# f1control.net
KiCad netlist of a schematic drawn in EAGLE
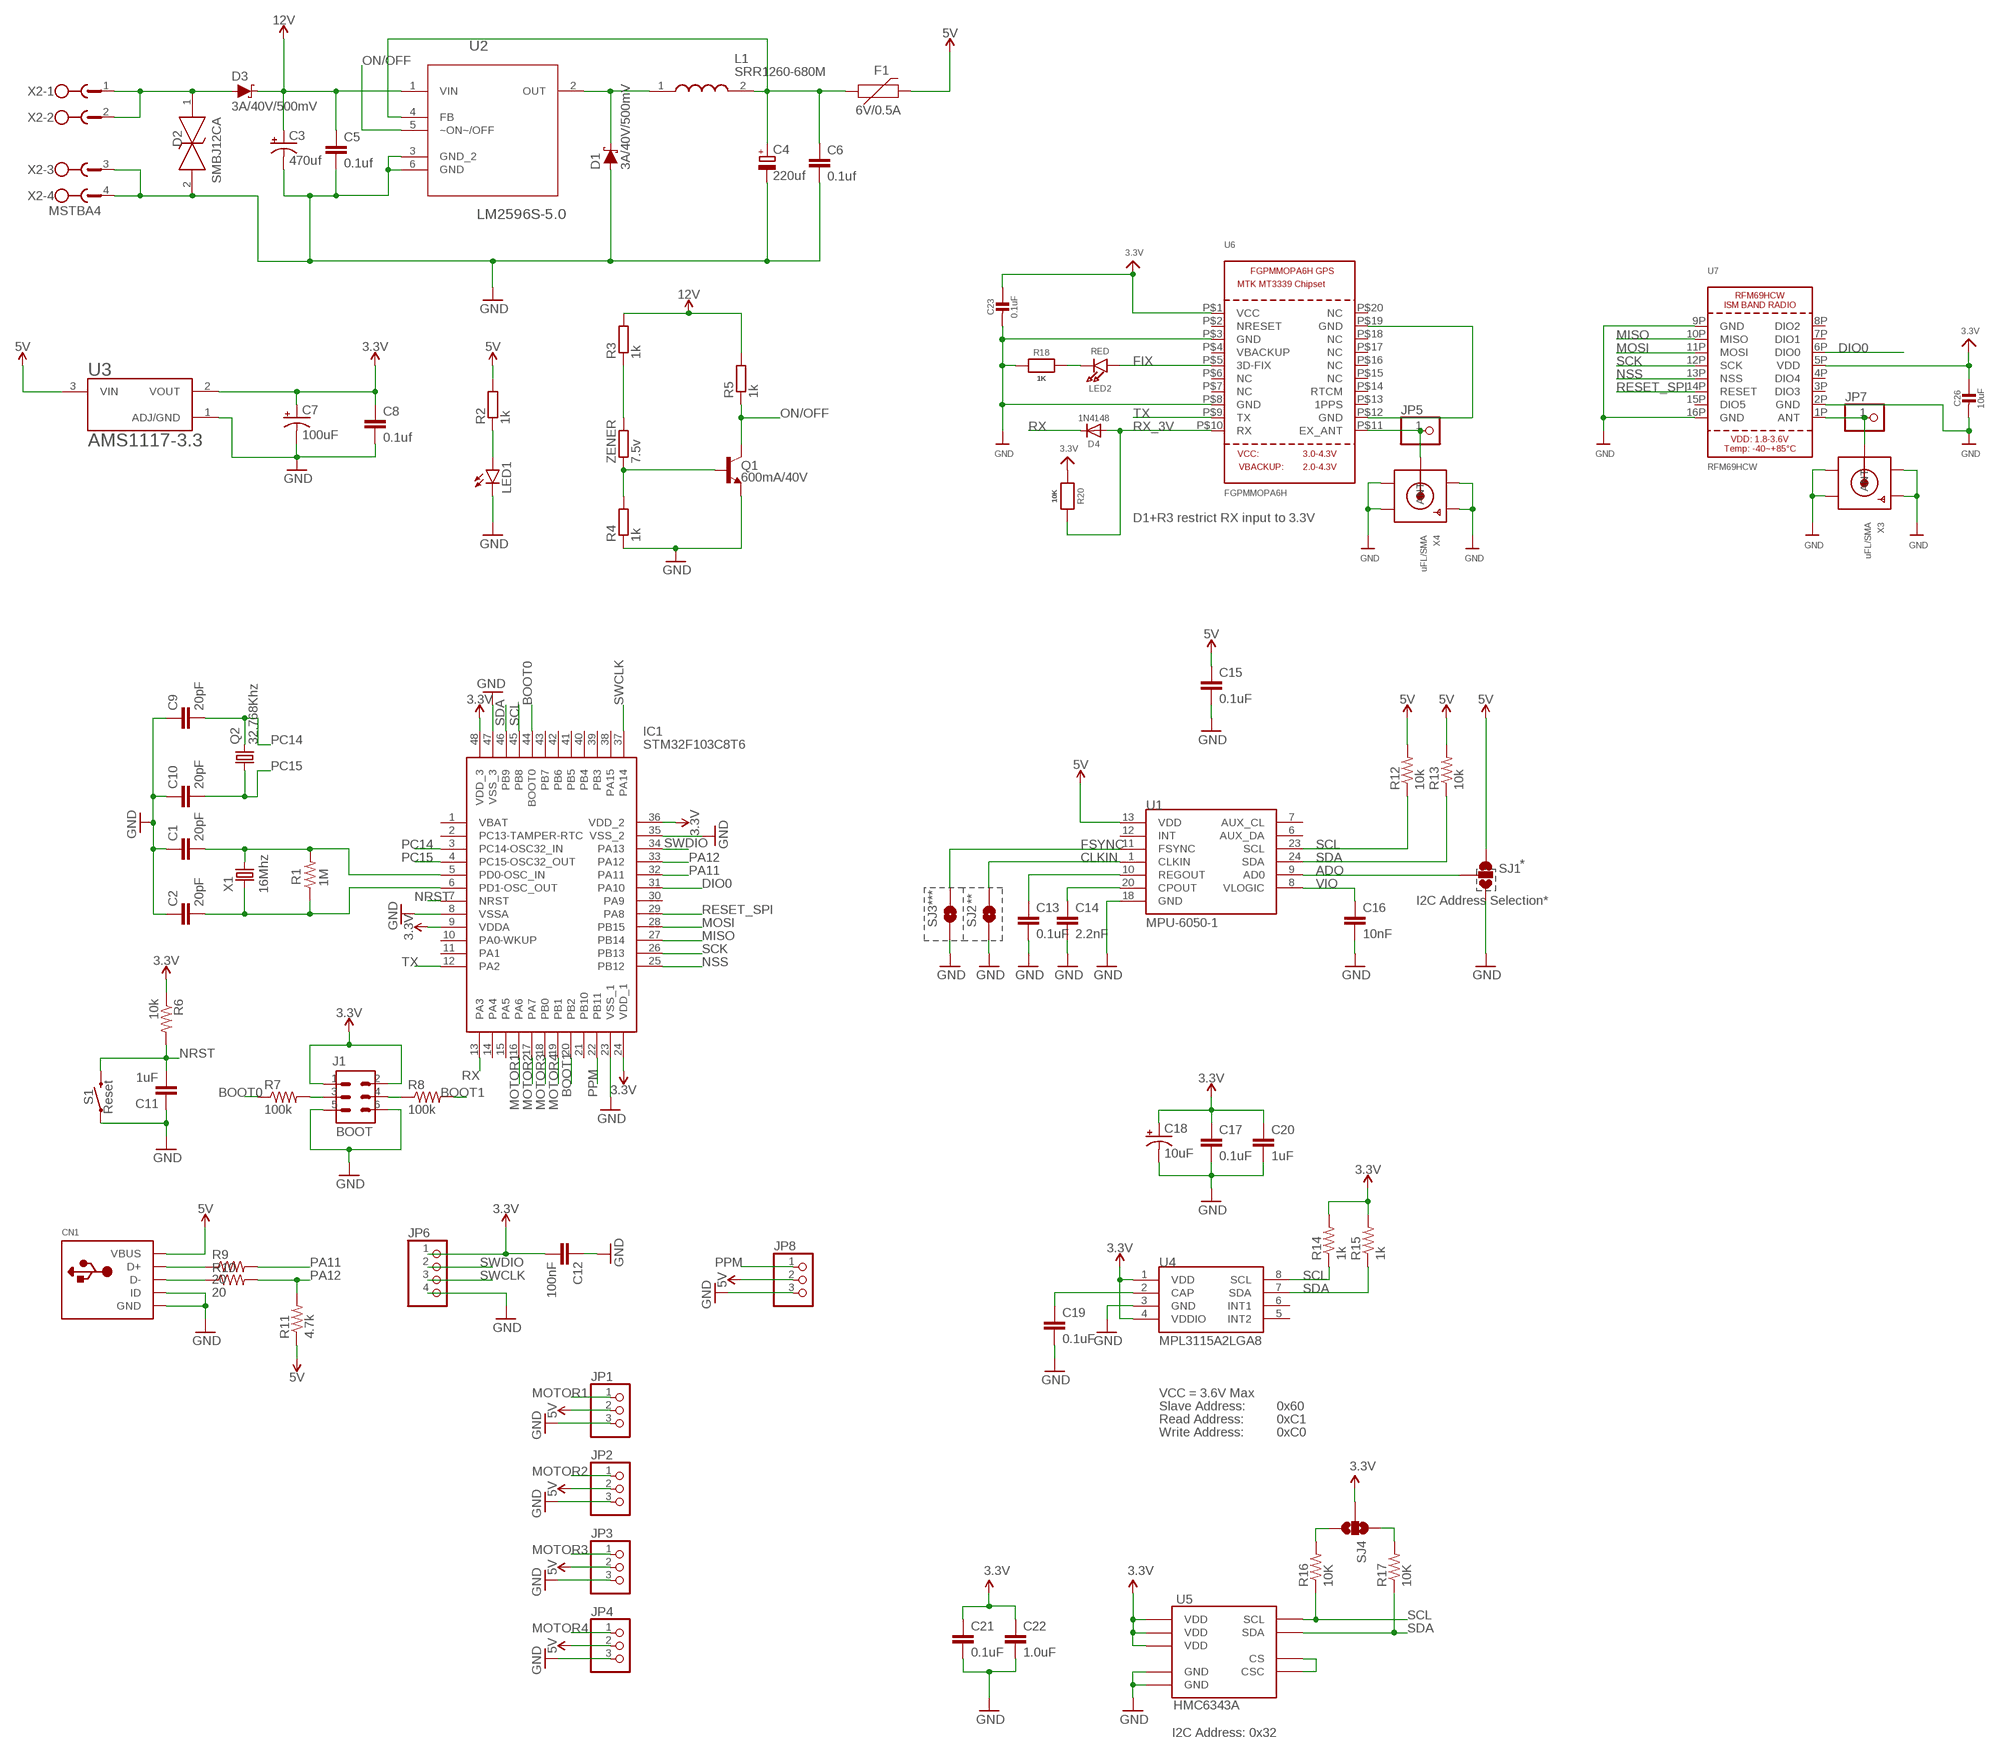
[diagram p0: schematic, sheet 1]

(export (version "E")
  (design (tool "Eeschema 10.0.6"))
  (components
    (comp (ref "C1")
      (value "20pF")
      (footprint "eagle-import:C0603")
      (libsource (lib "eagle-import") (part "C-EUC0603"))
    )
    (comp (ref "C2")
      (value "20pF")
      (footprint "eagle-import:C0603")
      (libsource (lib "eagle-import") (part "C-EUC0603"))
    )
    (comp (ref "C3")
      (value "470uf")
      (footprint "eagle-import:E5-8,5")
      (libsource (lib "eagle-import") (part "CPOL-USE5-8.5"))
    )
    (comp (ref "C4")
      (value "220uf")
      (footprint "eagle-import:153CLV-1014")
      (libsource (lib "eagle-import") (part "CPOL-EU153CLV-1014"))
    )
    (comp (ref "C5")
      (value "0.1uf")
      (footprint "eagle-import:C0805")
      (libsource (lib "eagle-import") (part "C-EUC0805"))
    )
    (comp (ref "C6")
      (value "0.1uf")
      (footprint "eagle-import:C0805")
      (libsource (lib "eagle-import") (part "C-EUC0805"))
    )
    (comp (ref "C7")
      (value "100uF")
      (footprint "eagle-import:NIC_10X10.5_CAP")
      (libsource (lib "eagle-import") (part "100UF-POLAR-10X10.5-63V-20%"))
    )
    (comp (ref "C8")
      (value "0.1uf")
      (footprint "eagle-import:C0805")
      (libsource (lib "eagle-import") (part "C-EUC0805"))
    )
    (comp (ref "C9")
      (value "20pF")
      (footprint "eagle-import:C0603")
      (libsource (lib "eagle-import") (part "C-EUC0603"))
    )
    (comp (ref "C10")
      (value "20pF")
      (footprint "eagle-import:C0603")
      (libsource (lib "eagle-import") (part "C-EUC0603"))
    )
    (comp (ref "C11")
      (value "1uF")
      (footprint "eagle-import:C0603")
      (libsource (lib "eagle-import") (part "C-EUC0603"))
    )
    (comp (ref "C12")
      (value "100nF")
      (footprint "eagle-import:C0603")
      (libsource (lib "eagle-import") (part "C-EUC0603"))
    )
    (comp (ref "C13")
      (value "0.1uF")
      (footprint "eagle-import:0603-CAP")
      (libsource (lib "eagle-import") (part "CAP0603-CAP"))
    )
    (comp (ref "C14")
      (value "2.2nF")
      (footprint "eagle-import:0603-CAP")
      (libsource (lib "eagle-import") (part "CAP0603-CAP"))
    )
    (comp (ref "C15")
      (value "0.1uF")
      (footprint "eagle-import:0603-CAP")
      (libsource (lib "eagle-import") (part "CAP0603-CAP"))
    )
    (comp (ref "C16")
      (value "10nF")
      (footprint "eagle-import:0603-CAP")
      (libsource (lib "eagle-import") (part "CAP0603-CAP"))
    )
    (comp (ref "C17")
      (value "0.1uF")
      (footprint "eagle-import:0402-CAP")
      (libsource (lib "eagle-import") (part "CAP0402-CAP"))
    )
    (comp (ref "C18")
      (value "10uF")
      (footprint "eagle-import:EIA3216")
      (libsource (lib "eagle-import") (part "CAP_POL1206"))
    )
    (comp (ref "C19")
      (value "0.1uF")
      (footprint "eagle-import:0402-CAP")
      (libsource (lib "eagle-import") (part "CAP0402-CAP"))
    )
    (comp (ref "C20")
      (value "1uF")
      (footprint "eagle-import:0402-CAP")
      (libsource (lib "eagle-import") (part "CAP0402-CAP"))
    )
    (comp (ref "C21")
      (value "0.1uF")
      (footprint "eagle-import:0603-CAP")
      (libsource (lib "eagle-import") (part "0.1UF-25V(+80/-20%)(0603)"))
    )
    (comp (ref "C22")
      (value "1.0uF")
      (footprint "eagle-import:0603-CAP")
      (libsource (lib "eagle-import") (part "1.0UF-16V-10%(0603)"))
    )
    (comp (ref "C23")
      (value "0.1uF")
      (footprint "eagle-import:0805-NO")
      (libsource (lib "eagle-import") (part "CAP_CERAMIC0805-NOOUTLINE"))
    )
    (comp (ref "C26")
      (value "10uF")
      (footprint "eagle-import:0805-NO")
      (libsource (lib "eagle-import") (part "CAP_CERAMIC0805-NOOUTLINE"))
    )
    (comp (ref "CN1")
      (value "USBMINIB")
      (footprint "eagle-import:USB-MINIB")
      (libsource (lib "eagle-import") (part "USBMINIB"))
    )
    (comp (ref "D1")
      (value "3A/40V/500mV")
      (footprint "eagle-import:SMA-DIODE")
      (libsource (lib "eagle-import") (part "DIODE-SCHOTTKY-B340A"))
    )
    (comp (ref "D2")
      (value "SMBJ12CA")
      (footprint "eagle-import:DIONM5443X244N")
      (fields (field (name "MOUSER_PART_NUMBER") "652-SMBJ12CA"))
      (libsource (lib "eagle-import") (part "SMBJ12CA"))
    )
    (comp (ref "D3")
      (value "3A/40V/500mV")
      (footprint "eagle-import:SMA-DIODE")
      (libsource (lib "eagle-import") (part "DIODE-SCHOTTKY-B340A"))
    )
    (comp (ref "D4")
      (value "1N4148")
      (footprint "eagle-import:SOD-323")
      (libsource (lib "eagle-import") (part "DIODESOD-323"))
    )
    (comp (ref "F1")
      (value "6V/0.5A")
      (footprint "eagle-import:1206")
      (libsource (lib "eagle-import") (part "PPTC_HALF-AMP"))
    )
    (comp (ref "IC1")
      (value "STM32F103C8T6")
      (footprint "eagle-import:QFP50P900X900X160-48N")
      (fields
        (field (name "MOUSER_PART_NUMBER") "511-STM32F103C8T6")
        (field (name "RS_PART_NUMBER") "0402279P")
      )
      (libsource (lib "eagle-import") (part "STM32F103C8T6"))
    )
    (comp (ref "J1")
      (value "BOOT")
      (footprint "eagle-import:621006245821")
      (fields
        (field (name "MANUFACTURER") "Wurth Elektronik")
        (field (name "MPN") "621006245821")
        (field (name "CREATED_BY") "PCBLayout.com")
      )
      (libsource (lib "eagle-import") (part "621006245821"))
    )
    (comp (ref "JP1")
      (value "PINHD-1X3")
      (footprint "eagle-import:1X03")
      (libsource (lib "eagle-import") (part "PINHD-1X3"))
    )
    (comp (ref "JP2")
      (value "PINHD-1X3")
      (footprint "eagle-import:1X03")
      (libsource (lib "eagle-import") (part "PINHD-1X3"))
    )
    (comp (ref "JP3")
      (value "PINHD-1X3")
      (footprint "eagle-import:1X03")
      (libsource (lib "eagle-import") (part "PINHD-1X3"))
    )
    (comp (ref "JP4")
      (value "PINHD-1X3")
      (footprint "eagle-import:1X03")
      (libsource (lib "eagle-import") (part "PINHD-1X3"))
    )
    (comp (ref "JP5")
      (value "HEADER-1X1ROUND")
      (footprint "eagle-import:1X01_ROUND")
      (libsource (lib "eagle-import") (part "HEADER-1X1ROUND"))
    )
    (comp (ref "JP6")
      (value "PINHD-1X4")
      (footprint "eagle-import:1X04")
      (libsource (lib "eagle-import") (part "PINHD-1X4"))
    )
    (comp (ref "JP7")
      (value "HEADER-1X1ROUND")
      (footprint "eagle-import:1X01_ROUND")
      (libsource (lib "eagle-import") (part "HEADER-1X1ROUND"))
    )
    (comp (ref "JP8")
      (value "PINHD-1X3")
      (footprint "eagle-import:1X03")
      (libsource (lib "eagle-import") (part "PINHD-1X3"))
    )
    (comp (ref "L1")
      (value "SRR1260-680M")
      (footprint "eagle-import:INDPM125125X650N")
      (fields
        (field (name "MOUSER_PART_NUMBER") "652-SRR1260-680M")
        (field (name "RS_PART_NUMBER") "7272243P")
      )
      (libsource (lib "eagle-import") (part "SRR1260-680M"))
    )
    (comp (ref "LED1")
      (value "LEDCHIP-LED0805")
      (footprint "eagle-import:CHIP-LED0805")
      (libsource (lib "eagle-import") (part "LEDCHIP-LED0805"))
    )
    (comp (ref "LED2")
      (value "RED")
      (footprint "eagle-import:CHIPLED_0805")
      (libsource (lib "eagle-import") (part "LED0805"))
    )
    (comp (ref "Q1")
      (value "600mA/40V")
      (footprint "eagle-import:SOT23-3")
      (libsource (lib "eagle-import") (part "TRANS_NPN-MMBT2222AL"))
    )
    (comp (ref "Q2")
      (value "32.768Khz")
      (footprint "eagle-import:MC-306")
      (fields (field (name "MPN") "MC-306 60.0KHZ  100PPM ,12.5PF"))
      (libsource (lib "eagle-import") (part "MC-306"))
    )
    (comp (ref "R1")
      (value "1M")
      (footprint "eagle-import:R0603")
      (libsource (lib "eagle-import") (part "R-US_R0603"))
    )
    (comp (ref "R2")
      (value "1k")
      (footprint "eagle-import:R0805")
      (libsource (lib "eagle-import") (part "R-EU_R0805"))
    )
    (comp (ref "R3")
      (value "1k")
      (footprint "eagle-import:R0805")
      (libsource (lib "eagle-import") (part "R-EU_R0805"))
    )
    (comp (ref "R4")
      (value "1k")
      (footprint "eagle-import:R0805")
      (libsource (lib "eagle-import") (part "R-EU_R0805"))
    )
    (comp (ref "R5")
      (value "1k")
      (footprint "eagle-import:R0805")
      (libsource (lib "eagle-import") (part "R-EU_R0805"))
    )
    (comp (ref "R6")
      (value "10k")
      (footprint "eagle-import:R0603")
      (libsource (lib "eagle-import") (part "R-US_R0603"))
    )
    (comp (ref "R7")
      (value "100k")
      (footprint "eagle-import:R0603")
      (libsource (lib "eagle-import") (part "R-US_R0603"))
    )
    (comp (ref "R8")
      (value "100k")
      (footprint "eagle-import:R0603")
      (libsource (lib "eagle-import") (part "R-US_R0603"))
    )
    (comp (ref "R9")
      (value "20")
      (footprint "eagle-import:R0603")
      (libsource (lib "eagle-import") (part "R-US_R0603"))
    )
    (comp (ref "R10")
      (value "20")
      (footprint "eagle-import:R0603")
      (libsource (lib "eagle-import") (part "R-US_R0603"))
    )
    (comp (ref "R11")
      (value "4.7k")
      (footprint "eagle-import:R0603")
      (libsource (lib "eagle-import") (part "R-US_R0603"))
    )
    (comp (ref "R12")
      (value "10k")
      (footprint "eagle-import:0603-RES")
      (libsource (lib "eagle-import") (part "RESISTOR0603-RES"))
    )
    (comp (ref "R13")
      (value "10k")
      (footprint "eagle-import:0603-RES")
      (libsource (lib "eagle-import") (part "RESISTOR0603-RES"))
    )
    (comp (ref "R14")
      (value "1k")
      (footprint "eagle-import:0402-RES")
      (libsource (lib "eagle-import") (part "RESISTOR0402-RES"))
    )
    (comp (ref "R15")
      (value "1k")
      (footprint "eagle-import:0402-RES")
      (libsource (lib "eagle-import") (part "RESISTOR0402-RES"))
    )
    (comp (ref "R16")
      (value "10K")
      (footprint "eagle-import:0603-RES")
      (libsource (lib "eagle-import") (part "10KOHM1/10W1%(0603)0603"))
    )
    (comp (ref "R17")
      (value "10K")
      (footprint "eagle-import:0603-RES")
      (libsource (lib "eagle-import") (part "10KOHM1/10W1%(0603)0603"))
    )
    (comp (ref "R18")
      (value "1K")
      (footprint "eagle-import:0805-NO")
      (libsource (lib "eagle-import") (part "RESISTOR0805_NOOUTLINE"))
    )
    (comp (ref "R20")
      (value "10K")
      (footprint "eagle-import:0805-NO")
      (libsource (lib "eagle-import") (part "RESISTOR0805_NOOUTLINE"))
    )
    (comp (ref "S1")
      (value "Reset")
      (footprint "eagle-import:TACTILE_SWITCH_SMD_4.5MM")
      (libsource (lib "eagle-import") (part "MOMENTARY-SWITCH-SPST-SMD-4.5MM"))
    )
    (comp (ref "SJ1")
      (value "SOLDERJUMPER_2WAYPASTE2&3")
      (footprint "eagle-import:SJ_3_PASTE2&3")
      (libsource (lib "eagle-import") (part "SOLDERJUMPER_2WAYPASTE2&3"))
    )
    (comp (ref "SJ2")
      (value "SOLDERJUMPERTRACE")
      (footprint "eagle-import:SJ_2S-TRACE")
      (libsource (lib "eagle-import") (part "SOLDERJUMPERTRACE"))
    )
    (comp (ref "SJ3")
      (value "SOLDERJUMPERTRACE")
      (footprint "eagle-import:SJ_2S-TRACE")
      (libsource (lib "eagle-import") (part "SOLDERJUMPERTRACE"))
    )
    (comp (ref "SJ4")
      (value "SOLDERJUMPER_2WAYPASTE1&2&3")
      (footprint "eagle-import:SJ_3_PASTE1&2&3")
      (libsource (lib "eagle-import") (part "SOLDERJUMPER_2WAYPASTE1&2&3"))
    )
    (comp (ref "U1")
      (value "MPU-6050-1")
      (footprint "eagle-import:QFN-24-4MM2")
      (libsource (lib "eagle-import") (part "MPU-6050-1"))
    )
    (comp (ref "U2")
      (value "LM2596S-5.0")
      (footprint "eagle-import:TO170P1435X465-6N")
      (fields (field (name "MF") "Texas"))
      (libsource (lib "eagle-import") (part "LM2596S-5.0"))
    )
    (comp (ref "U3")
      (value "AMS1117-3.3")
      (footprint "eagle-import:SOT229P700X180-4N")
      (fields (field (name "MF") "Advanced Monolithic Systems"))
      (libsource (lib "eagle-import") (part "AMS1117-3.3"))
    )
    (comp (ref "U4")
      (value "MPL3115A2LGA8")
      (footprint "eagle-import:LGA8")
      (libsource (lib "eagle-import") (part "MPL3115A2LGA8"))
    )
    (comp (ref "U5")
      (value "HMC6343A")
      (footprint "eagle-import:LCC36")
      (libsource (lib "eagle-import") (part "HMC6343A"))
    )
    (comp (ref "U6")
      (value "FGPMMOPA6H")
      (footprint "eagle-import:FGPMMOPA6H")
      (libsource (lib "eagle-import") (part "GPS_FGPMMOPA6H"))
    )
    (comp (ref "U7")
      (value "RFM69HCW")
      (footprint "eagle-import:RFMHCW_SMT")
      (libsource (lib "eagle-import") (part "RFM69HCW_SMT"))
    )
    (comp (ref "X1")
      (value "16Mhz")
      (footprint "eagle-import:XTAL_HC49")
      (fields
        (field (name "MANUFACTURER") "Xinhunjing ")
        (field (name "MPN") "49S/18PF")
        (field (name "CREATED_BY") "PCBLayout.com")
      )
      (libsource (lib "eagle-import") (part "49S/18PF"))
    )
    (comp (ref "X2")
      (value "MSTBA4")
      (footprint "eagle-import:MSTBA4")
      (fields (field (name "MF") "FARNELL") (field (name "MPN") "1757268"))
      (libsource (lib "eagle-import") (part "MSTBA4"))
    )
    (comp (ref "X3")
      (value "uFL/SMA")
      (footprint "eagle-import:SMA_EDGELAUNCH_UFL")
      (libsource (lib "eagle-import") (part "SMACONNECTOR_EDGE_UFL"))
    )
    (comp (ref "X4")
      (value "uFL/SMA")
      (footprint "eagle-import:SMA_EDGELAUNCH_UFL")
      (libsource (lib "eagle-import") (part "SMACONNECTOR_EDGE_UFL"))
    )
    (comp (ref "ZENER")
      (value "7.5v")
      (footprint "eagle-import:0204_7")
      (libsource (lib "eagle-import") (part "R-EU_0204/7"))
    )
  )
  (nets
    (net (code "1") (name "/ADO") (class "Default")
      (node (ref "SJ1") (pin "2") (pinfunction "2_2") (pintype "passive"))
      (node (ref "U1") (pin "9") (pinfunction "AD0_9") (pintype "bidirectional"))
    )
    (net (code "2") (name "/BOOT0") (class "Default")
      (node (ref "IC1") (pin "44") (pinfunction "BOOT0_44") (pintype "bidirectional"))
      (node (ref "R7") (pin "1") (pinfunction "1_1") (pintype "passive"))
    )
    (net (code "3") (name "/BOOT1") (class "Default")
      (node (ref "IC1") (pin "20") (pinfunction "PB2_20") (pintype "bidirectional"))
      (node (ref "R8") (pin "2") (pinfunction "2_2") (pintype "passive"))
    )
    (net (code "4") (name "/CLKIN") (class "Default")
      (node (ref "SJ2") (pin "2") (pinfunction "2_2") (pintype "passive"))
      (node (ref "U1") (pin "1") (pinfunction "CLKIN_1") (pintype "bidirectional"))
    )
    (net (code "5") (name "/DIO0") (class "Default")
      (node (ref "IC1") (pin "31") (pinfunction "PA10_31") (pintype "bidirectional"))
      (node (ref "U7") (pin "6P") (pinfunction "DIO0_6P") (pintype "bidirectional"))
    )
    (net (code "6") (name "/FIX") (class "Default")
      (node (ref "LED2") (pin "A") (pinfunction "A_A") (pintype "passive"))
      (node (ref "U6") (pin "P$5") (pinfunction "3D-FIX_P$5") (pintype "bidirectional"))
    )
    (net (code "7") (name "/FSYNC") (class "Default")
      (node (ref "SJ3") (pin "2") (pinfunction "2_2") (pintype "passive"))
      (node (ref "U1") (pin "11") (pinfunction "FSYNC_11") (pintype "bidirectional"))
    )
    (net (code "8") (name "/MISO") (class "Default")
      (node (ref "IC1") (pin "27") (pinfunction "PB14_27") (pintype "bidirectional"))
      (node (ref "U7") (pin "10P") (pinfunction "MISO_10P") (pintype "output"))
    )
    (net (code "9") (name "/MOSI") (class "Default")
      (node (ref "IC1") (pin "28") (pinfunction "PB15_28") (pintype "bidirectional"))
      (node (ref "U7") (pin "11P") (pinfunction "MOSI_11P") (pintype "input"))
    )
    (net (code "10") (name "/MOTOR1") (class "Default")
      (node (ref "IC1") (pin "16") (pinfunction "PA6_16") (pintype "bidirectional"))
      (node (ref "JP1") (pin "1") (pinfunction "1_1") (pintype "passive"))
    )
    (net (code "11") (name "/MOTOR2") (class "Default")
      (node (ref "IC1") (pin "17") (pinfunction "PA7_17") (pintype "bidirectional"))
      (node (ref "JP2") (pin "1") (pinfunction "1_1") (pintype "passive"))
    )
    (net (code "12") (name "/MOTOR3") (class "Default")
      (node (ref "IC1") (pin "18") (pinfunction "PB0_18") (pintype "bidirectional"))
      (node (ref "JP3") (pin "1") (pinfunction "1_1") (pintype "passive"))
    )
    (net (code "13") (name "/MOTOR4") (class "Default")
      (node (ref "IC1") (pin "19") (pinfunction "PB1_19") (pintype "bidirectional"))
      (node (ref "JP4") (pin "1") (pinfunction "1_1") (pintype "passive"))
    )
    (net (code "14") (name "/NRST") (class "Default")
      (node (ref "C11") (pin "2") (pinfunction "2_2") (pintype "passive"))
      (node (ref "IC1") (pin "7") (pinfunction "NRST_7") (pintype "input"))
      (node (ref "R6") (pin "2") (pinfunction "2_2") (pintype "passive"))
      (node (ref "S1") (pin "1") (pinfunction "2_1") (pintype "passive"))
      (node (ref "S1") (pin "4") (pinfunction "2_4") (pintype "passive"))
    )
    (net (code "15") (name "/NSS") (class "Default")
      (node (ref "IC1") (pin "25") (pinfunction "PB12_25") (pintype "bidirectional"))
      (node (ref "U7") (pin "13P") (pinfunction "NSS_13P") (pintype "input"))
    )
    (net (code "16") (name "/ON{slash}OFF") (class "Default")
      (node (ref "Q1") (pin "3") (pinfunction "C_3") (pintype "passive"))
      (node (ref "R5") (pin "1") (pinfunction "1_1") (pintype "passive"))
      (node (ref "U2") (pin "5") (pinfunction "~{ON}/OFF_5") (pintype "input"))
    )
    (net (code "17") (name "/PA11") (class "Default")
      (node (ref "IC1") (pin "32") (pinfunction "PA11_32") (pintype "bidirectional"))
      (node (ref "R9") (pin "2") (pinfunction "2_2") (pintype "passive"))
    )
    (net (code "18") (name "/PA12") (class "Default")
      (node (ref "IC1") (pin "33") (pinfunction "PA12_33") (pintype "bidirectional"))
      (node (ref "R10") (pin "2") (pinfunction "2_2") (pintype "passive"))
      (node (ref "R11") (pin "2") (pinfunction "2_2") (pintype "passive"))
    )
    (net (code "19") (name "/PC14") (class "Default")
      (node (ref "C9") (pin "2") (pinfunction "2_2") (pintype "passive"))
      (node (ref "IC1") (pin "3") (pinfunction "PC14-OSC32_IN_3") (pintype "input"))
      (node (ref "Q2") (pin "4") (pinfunction "2_4") (pintype "passive"))
    )
    (net (code "20") (name "/PC15") (class "Default")
      (node (ref "C10") (pin "2") (pinfunction "2_2") (pintype "passive"))
      (node (ref "IC1") (pin "4") (pinfunction "PC15-OSC32_OUT_4") (pintype "output"))
      (node (ref "Q2") (pin "1") (pinfunction "1_1") (pintype "passive"))
    )
    (net (code "21") (name "/PPM") (class "Default")
      (node (ref "IC1") (pin "22") (pinfunction "PB11_22") (pintype "bidirectional"))
      (node (ref "JP8") (pin "1") (pinfunction "1_1") (pintype "passive"))
    )
    (net (code "22") (name "/RESET_SPI") (class "Default")
      (node (ref "IC1") (pin "29") (pinfunction "PA8_29") (pintype "bidirectional"))
      (node (ref "U7") (pin "14P") (pinfunction "RESET_14P") (pintype "input"))
    )
    (net (code "23") (name "/RX") (class "Default")
      (node (ref "D4") (pin "C") (pinfunction "C_C") (pintype "passive"))
      (node (ref "IC1") (pin "13") (pinfunction "PA3_13") (pintype "bidirectional"))
    )
    (net (code "24") (name "/RX_3V") (class "Default")
      (node (ref "D4") (pin "A") (pinfunction "A_A") (pintype "passive"))
      (node (ref "R20") (pin "2") (pinfunction "2_2") (pintype "passive"))
      (node (ref "U6") (pin "P$10") (pinfunction "RX_P$10") (pintype "bidirectional"))
    )
    (net (code "25") (name "/SCK") (class "Default")
      (node (ref "IC1") (pin "26") (pinfunction "PB13_26") (pintype "bidirectional"))
      (node (ref "U7") (pin "12P") (pinfunction "SCK_12P") (pintype "input"))
    )
    (net (code "26") (name "/SCL") (class "Default")
      (node (ref "IC1") (pin "45") (pinfunction "PB8_45") (pintype "bidirectional"))
      (node (ref "R12") (pin "1") (pinfunction "1_1") (pintype "passive"))
      (node (ref "R14") (pin "1") (pinfunction "1_1") (pintype "passive"))
      (node (ref "R16") (pin "1") (pinfunction "1_1") (pintype "passive"))
      (node (ref "U1") (pin "23") (pinfunction "SCL_23") (pintype "bidirectional"))
      (node (ref "U4") (pin "8") (pinfunction "SCL_8") (pintype "bidirectional"))
      (node (ref "U5") (pin "32") (pinfunction "SCL_32") (pintype "bidirectional"))
    )
    (net (code "27") (name "/SDA") (class "Default")
      (node (ref "IC1") (pin "46") (pinfunction "PB9_46") (pintype "bidirectional"))
      (node (ref "R13") (pin "1") (pinfunction "1_1") (pintype "passive"))
      (node (ref "R15") (pin "1") (pinfunction "1_1") (pintype "passive"))
      (node (ref "R17") (pin "1") (pinfunction "1_1") (pintype "passive"))
      (node (ref "U1") (pin "24") (pinfunction "SDA_24") (pintype "bidirectional"))
      (node (ref "U4") (pin "7") (pinfunction "SDA_7") (pintype "bidirectional"))
      (node (ref "U5") (pin "36") (pinfunction "SDA_36") (pintype "bidirectional"))
    )
    (net (code "28") (name "/SWCLK") (class "Default")
      (node (ref "IC1") (pin "37") (pinfunction "PA14_37") (pintype "bidirectional"))
      (node (ref "JP6") (pin "3") (pinfunction "3_3") (pintype "passive"))
    )
    (net (code "29") (name "/SWDIO") (class "Default")
      (node (ref "IC1") (pin "34") (pinfunction "PA13_34") (pintype "bidirectional"))
      (node (ref "JP6") (pin "2") (pinfunction "2_2") (pintype "passive"))
    )
    (net (code "30") (name "/TX") (class "Default")
      (node (ref "IC1") (pin "12") (pinfunction "PA2_12") (pintype "bidirectional"))
      (node (ref "U6") (pin "P$9") (pinfunction "TX_P$9") (pintype "bidirectional"))
    )
    (net (code "31") (name "/VIO") (class "Default")
      (node (ref "C16") (pin "1") (pinfunction "1_1") (pintype "passive"))
      (node (ref "U1") (pin "8") (pinfunction "VLOGIC_8") (pintype "bidirectional"))
    )
    (net (code "32") (name "3.3V") (class "Default")
      (node (ref "C12") (pin "2") (pinfunction "2_2") (pintype "passive"))
      (node (ref "C17") (pin "1") (pinfunction "1_1") (pintype "passive"))
      (node (ref "C18") (pin "A") (pinfunction "+_A") (pintype "passive"))
      (node (ref "C20") (pin "1") (pinfunction "1_1") (pintype "passive"))
      (node (ref "C21") (pin "1") (pinfunction "1_1") (pintype "passive"))
      (node (ref "C22") (pin "1") (pinfunction "1_1") (pintype "passive"))
      (node (ref "C23") (pin "1") (pinfunction "1_1") (pintype "passive"))
      (node (ref "C26") (pin "1") (pinfunction "1_1") (pintype "passive"))
      (node (ref "C7") (pin "+") (pinfunction "+_+") (pintype "passive"))
      (node (ref "C8") (pin "1") (pinfunction "1_1") (pintype "passive"))
      (node (ref "IC1") (pin "24") (pinfunction "VDD_1_24") (pintype "power_in"))
      (node (ref "IC1") (pin "36") (pinfunction "VDD_2_36") (pintype "power_in"))
      (node (ref "IC1") (pin "48") (pinfunction "VDD_3_48") (pintype "power_in"))
      (node (ref "IC1") (pin "9") (pinfunction "VDDA_9") (pintype "power_in"))
      (node (ref "J1") (pin "1") (pinfunction "1_1") (pintype "passive"))
      (node (ref "J1") (pin "2") (pinfunction "2_2") (pintype "passive"))
      (node (ref "JP6") (pin "1") (pinfunction "1_1") (pintype "passive"))
      (node (ref "R14") (pin "2") (pinfunction "2_2") (pintype "passive"))
      (node (ref "R15") (pin "2") (pinfunction "2_2") (pintype "passive"))
      (node (ref "R20") (pin "1") (pinfunction "1_1") (pintype "passive"))
      (node (ref "R6") (pin "1") (pinfunction "1_1") (pintype "passive"))
      (node (ref "SJ4") (pin "2") (pinfunction "2_2") (pintype "passive"))
      (node (ref "U3") (pin "2") (pinfunction "VOUT_2") (pintype "output"))
      (node (ref "U4") (pin "1") (pinfunction "VDD_1") (pintype "bidirectional"))
      (node (ref "U4") (pin "4") (pinfunction "VDDIO_4") (pintype "bidirectional"))
      (node (ref "U5") (pin "11") (pinfunction "VDD_11") (pintype "bidirectional"))
      (node (ref "U5") (pin "21") (pinfunction "VDD_21") (pintype "bidirectional"))
      (node (ref "U5") (pin "3") (pinfunction "VDD_3") (pintype "bidirectional"))
      (node (ref "U6") (pin "P$1") (pinfunction "VCC_P$1") (pintype "bidirectional"))
      (node (ref "U7") (pin "5P") (pinfunction "VDD_5P") (pintype "power_in"))
    )
    (net (code "33") (name "5V") (class "Default")
      (node (ref "C15") (pin "1") (pinfunction "1_1") (pintype "passive"))
      (node (ref "CN1") (pin "VBUS") (pinfunction "VBUS_VBUS") (pintype "power_in"))
      (node (ref "F1") (pin "2") (pinfunction "2_2") (pintype "bidirectional"))
      (node (ref "JP1") (pin "2") (pinfunction "2_2") (pintype "passive"))
      (node (ref "JP2") (pin "2") (pinfunction "2_2") (pintype "passive"))
      (node (ref "JP3") (pin "2") (pinfunction "2_2") (pintype "passive"))
      (node (ref "JP4") (pin "2") (pinfunction "2_2") (pintype "passive"))
      (node (ref "JP8") (pin "2") (pinfunction "2_2") (pintype "passive"))
      (node (ref "R11") (pin "1") (pinfunction "1_1") (pintype "passive"))
      (node (ref "R12") (pin "2") (pinfunction "2_2") (pintype "passive"))
      (node (ref "R13") (pin "2") (pinfunction "2_2") (pintype "passive"))
      (node (ref "R2") (pin "2") (pinfunction "2_2") (pintype "passive"))
      (node (ref "SJ1") (pin "1") (pinfunction "1_1") (pintype "passive"))
      (node (ref "U1") (pin "13") (pinfunction "VDD_13") (pintype "bidirectional"))
      (node (ref "U3") (pin "3") (pinfunction "VIN_3") (pintype "input"))
    )
    (net (code "34") (name "12V") (class "Default")
      (node (ref "C3") (pin "+") (pinfunction "+_+") (pintype "passive"))
      (node (ref "C5") (pin "1") (pinfunction "1_1") (pintype "passive"))
      (node (ref "D3") (pin "C") (pinfunction "C_C") (pintype "passive"))
      (node (ref "R3") (pin "2") (pinfunction "2_2") (pintype "passive"))
      (node (ref "R5") (pin "2") (pinfunction "2_2") (pintype "passive"))
      (node (ref "U2") (pin "1") (pinfunction "VIN_1") (pintype "power_in"))
    )
    (net (code "35") (name "GND") (class "Default")
      (node (ref "C1") (pin "1") (pinfunction "1_1") (pintype "passive"))
      (node (ref "C10") (pin "1") (pinfunction "1_1") (pintype "passive"))
      (node (ref "C11") (pin "1") (pinfunction "1_1") (pintype "passive"))
      (node (ref "C12") (pin "1") (pinfunction "1_1") (pintype "passive"))
      (node (ref "C13") (pin "2") (pinfunction "2_2") (pintype "passive"))
      (node (ref "C14") (pin "2") (pinfunction "2_2") (pintype "passive"))
      (node (ref "C15") (pin "2") (pinfunction "2_2") (pintype "passive"))
      (node (ref "C16") (pin "2") (pinfunction "2_2") (pintype "passive"))
      (node (ref "C17") (pin "2") (pinfunction "2_2") (pintype "passive"))
      (node (ref "C18") (pin "C") (pinfunction "-_C") (pintype "passive"))
      (node (ref "C19") (pin "2") (pinfunction "2_2") (pintype "passive"))
      (node (ref "C2") (pin "1") (pinfunction "1_1") (pintype "passive"))
      (node (ref "C20") (pin "2") (pinfunction "2_2") (pintype "passive"))
      (node (ref "C21") (pin "2") (pinfunction "2_2") (pintype "passive"))
      (node (ref "C22") (pin "2") (pinfunction "2_2") (pintype "passive"))
      (node (ref "C23") (pin "2") (pinfunction "2_2") (pintype "passive"))
      (node (ref "C26") (pin "2") (pinfunction "2_2") (pintype "passive"))
      (node (ref "C3") (pin "-") (pinfunction "-_-") (pintype "passive"))
      (node (ref "C4") (pin "-") (pinfunction "-_-") (pintype "passive"))
      (node (ref "C5") (pin "2") (pinfunction "2_2") (pintype "passive"))
      (node (ref "C6") (pin "2") (pinfunction "2_2") (pintype "passive"))
      (node (ref "C7") (pin "-") (pinfunction "-_-") (pintype "passive"))
      (node (ref "C8") (pin "2") (pinfunction "2_2") (pintype "passive"))
      (node (ref "C9") (pin "1") (pinfunction "1_1") (pintype "passive"))
      (node (ref "CN1") (pin "GND") (pinfunction "GND_GND") (pintype "power_in"))
      (node (ref "CN1") (pin "ID") (pinfunction "ID_ID") (pintype "bidirectional"))
      (node (ref "D1") (pin "A") (pinfunction "A_A") (pintype "passive"))
      (node (ref "D2") (pin "2") (pinfunction "2_2") (pintype "bidirectional"))
      (node (ref "IC1") (pin "23") (pinfunction "VSS_1_23") (pintype "power_in"))
      (node (ref "IC1") (pin "35") (pinfunction "VSS_2_35") (pintype "power_in"))
      (node (ref "IC1") (pin "47") (pinfunction "VSS_3_47") (pintype "power_in"))
      (node (ref "IC1") (pin "8") (pinfunction "VSSA_8") (pintype "power_in"))
      (node (ref "J1") (pin "5") (pinfunction "5_5") (pintype "passive"))
      (node (ref "J1") (pin "6") (pinfunction "6_6") (pintype "passive"))
      (node (ref "JP1") (pin "3") (pinfunction "3_3") (pintype "passive"))
      (node (ref "JP2") (pin "3") (pinfunction "3_3") (pintype "passive"))
      (node (ref "JP3") (pin "3") (pinfunction "3_3") (pintype "passive"))
      (node (ref "JP4") (pin "3") (pinfunction "3_3") (pintype "passive"))
      (node (ref "JP6") (pin "4") (pinfunction "4_4") (pintype "passive"))
      (node (ref "JP8") (pin "3") (pinfunction "3_3") (pintype "passive"))
      (node (ref "LED1") (pin "C") (pinfunction "C_C") (pintype "passive"))
      (node (ref "Q1") (pin "2") (pinfunction "E_2") (pintype "passive"))
      (node (ref "R18") (pin "1") (pinfunction "1_1") (pintype "passive"))
      (node (ref "R4") (pin "1") (pinfunction "1_1") (pintype "passive"))
      (node (ref "S1") (pin "2") (pinfunction "1_2") (pintype "passive"))
      (node (ref "S1") (pin "3") (pinfunction "1_3") (pintype "passive"))
      (node (ref "SJ1") (pin "3") (pinfunction "3_3") (pintype "passive"))
      (node (ref "SJ2") (pin "1") (pinfunction "1_1") (pintype "passive"))
      (node (ref "SJ3") (pin "1") (pinfunction "1_1") (pintype "passive"))
      (node (ref "U1") (pin "18") (pinfunction "GND_18") (pintype "bidirectional"))
      (node (ref "U2") (pin "3") (pinfunction "GND_2_3") (pintype "passive"))
      (node (ref "U2") (pin "6") (pinfunction "GND_6") (pintype "passive"))
      (node (ref "U3") (pin "1") (pinfunction "ADJ/GND_1") (pintype "power_in"))
      (node (ref "U4") (pin "3") (pinfunction "GND_3") (pintype "bidirectional"))
      (node (ref "U5") (pin "25") (pinfunction "GND_25") (pintype "bidirectional"))
      (node (ref "U5") (pin "29") (pinfunction "GND_29") (pintype "bidirectional"))
      (node (ref "U6") (pin "P$3") (pinfunction "GND_P$3") (pintype "bidirectional"))
      (node (ref "U6") (pin "P$8") (pinfunction "GND_P$8") (pintype "bidirectional"))
      (node (ref "U7") (pin "16P") (pinfunction "GND_16P") (pintype "power_in"))
      (node (ref "U7") (pin "2P") (pinfunction "GND_2P") (pintype "power_in"))
      (node (ref "U7") (pin "9P") (pinfunction "GND_9P") (pintype "power_in"))
      (node (ref "X2") (pin "3") (pinfunction "1_3") (pintype "passive"))
      (node (ref "X2") (pin "4") (pinfunction "1_4") (pintype "passive"))
      (node (ref "X3") (pin "GND@1") (pinfunction "GND1_GND@1") (pintype "power_in"))
      (node (ref "X3") (pin "GND@2") (pinfunction "GND2_GND@2") (pintype "power_in"))
      (node (ref "X3") (pin "GND@3") (pinfunction "GND3_GND@3") (pintype "power_in"))
      (node (ref "X3") (pin "GND@4") (pinfunction "GND4_GND@4") (pintype "power_in"))
      (node (ref "X4") (pin "GND@1") (pinfunction "GND1_GND@1") (pintype "power_in"))
      (node (ref "X4") (pin "GND@2") (pinfunction "GND2_GND@2") (pintype "power_in"))
      (node (ref "X4") (pin "GND@3") (pinfunction "GND3_GND@3") (pintype "power_in"))
      (node (ref "X4") (pin "GND@4") (pinfunction "GND4_GND@4") (pintype "power_in"))
    )
    (net (code "36") (name "Net-(CN1-PadD+)") (class "Default")
      (node (ref "CN1") (pin "D+") (pinfunction "D+_D+") (pintype "bidirectional"))
      (node (ref "R9") (pin "1") (pinfunction "1_1") (pintype "passive"))
    )
    (net (code "37") (name "Net-(CN1-PadD-)") (class "Default")
      (node (ref "CN1") (pin "D-") (pinfunction "D-_D-") (pintype "bidirectional"))
      (node (ref "R10") (pin "1") (pinfunction "1_1") (pintype "passive"))
    )
    (net (code "38") (name "Net-(IC1-PD0-OSC_IN)") (class "Default")
      (node (ref "C1") (pin "2") (pinfunction "2_2") (pintype "passive"))
      (node (ref "IC1") (pin "5") (pinfunction "PD0-OSC_IN_5") (pintype "input"))
      (node (ref "R1") (pin "2") (pinfunction "2_2") (pintype "passive"))
      (node (ref "X1") (pin "2") (pinfunction "2_2") (pintype "passive"))
    )
    (net (code "39") (name "Net-(IC1-PD1-OSC_OUT)") (class "Default")
      (node (ref "C2") (pin "2") (pinfunction "2_2") (pintype "passive"))
      (node (ref "IC1") (pin "6") (pinfunction "PD1-OSC_OUT_6") (pintype "output"))
      (node (ref "R1") (pin "1") (pinfunction "1_1") (pintype "passive"))
      (node (ref "X1") (pin "1") (pinfunction "1_1") (pintype "passive"))
    )
    (net (code "40") (name "Net-(J1-Pad3)") (class "Default")
      (node (ref "J1") (pin "3") (pinfunction "3_3") (pintype "passive"))
      (node (ref "R7") (pin "2") (pinfunction "2_2") (pintype "passive"))
    )
    (net (code "41") (name "Net-(J1-Pad4)") (class "Default")
      (node (ref "J1") (pin "4") (pinfunction "4_4") (pintype "passive"))
      (node (ref "R8") (pin "1") (pinfunction "1_1") (pintype "passive"))
    )
    (net (code "42") (name "Net-(LED1-PadA)") (class "Default")
      (node (ref "LED1") (pin "A") (pinfunction "A_A") (pintype "passive"))
      (node (ref "R2") (pin "1") (pinfunction "1_1") (pintype "passive"))
    )
    (net (code "43") (name "Net-(LED2-PadC)") (class "Default")
      (node (ref "LED2") (pin "C") (pinfunction "C_C") (pintype "passive"))
      (node (ref "R18") (pin "2") (pinfunction "2_2") (pintype "passive"))
    )
    (net (code "44") (name "Net-(Q1-B)") (class "Default")
      (node (ref "Q1") (pin "1") (pinfunction "B_1") (pintype "passive"))
      (node (ref "R4") (pin "2") (pinfunction "2_2") (pintype "passive"))
      (node (ref "ZENER") (pin "1") (pinfunction "1_1") (pintype "passive"))
    )
    (net (code "45") (name "Net-(R3-Pad1)") (class "Default")
      (node (ref "R3") (pin "1") (pinfunction "1_1") (pintype "passive"))
      (node (ref "ZENER") (pin "2") (pinfunction "2_2") (pintype "passive"))
    )
    (net (code "46") (name "Net-(R16-Pad2)") (class "Default")
      (node (ref "R16") (pin "2") (pinfunction "2_2") (pintype "passive"))
      (node (ref "SJ4") (pin "3") (pinfunction "3_3") (pintype "passive"))
    )
    (net (code "47") (name "Net-(R17-Pad2)") (class "Default")
      (node (ref "R17") (pin "2") (pinfunction "2_2") (pintype "passive"))
      (node (ref "SJ4") (pin "1") (pinfunction "1_1") (pintype "passive"))
    )
    (net (code "48") (name "Net-(U1-CPOUT)") (class "Default")
      (node (ref "C14") (pin "1") (pinfunction "1_1") (pintype "passive"))
      (node (ref "U1") (pin "20") (pinfunction "CPOUT_20") (pintype "bidirectional"))
    )
    (net (code "49") (name "Net-(U1-REGOUT)") (class "Default")
      (node (ref "C13") (pin "1") (pinfunction "1_1") (pintype "passive"))
      (node (ref "U1") (pin "10") (pinfunction "REGOUT_10") (pintype "bidirectional"))
    )
    (net (code "50") (name "Net-(U2-FB)") (class "Default")
      (node (ref "C4") (pin "+") (pinfunction "+_+") (pintype "passive"))
      (node (ref "C6") (pin "1") (pinfunction "1_1") (pintype "passive"))
      (node (ref "F1") (pin "1") (pinfunction "1_1") (pintype "bidirectional"))
      (node (ref "L1") (pin "2") (pinfunction "2_2") (pintype "bidirectional"))
      (node (ref "U2") (pin "4") (pinfunction "FB_4") (pintype "input"))
    )
    (net (code "51") (name "Net-(U2-OUT)") (class "Default")
      (node (ref "D1") (pin "C") (pinfunction "C_C") (pintype "passive"))
      (node (ref "L1") (pin "1") (pinfunction "1_1") (pintype "bidirectional"))
      (node (ref "U2") (pin "2") (pinfunction "OUT_2") (pintype "output"))
    )
    (net (code "52") (name "Net-(U4-CAP)") (class "Default")
      (node (ref "C19") (pin "1") (pinfunction "1_1") (pintype "passive"))
      (node (ref "U4") (pin "2") (pinfunction "CAP_2") (pintype "bidirectional"))
    )
    (net (code "53") (name "Net-(U5-CS)") (class "Default")
      (node (ref "U5") (pin "22") (pinfunction "CS_22") (pintype "bidirectional"))
      (node (ref "U5") (pin "35") (pinfunction "CSC_35") (pintype "bidirectional"))
    )
    (net (code "54") (name "Net-(U6-EX_ANT)") (class "Default")
      (node (ref "JP5") (pin "1") (pinfunction "1_1") (pintype "passive"))
      (node (ref "U6") (pin "P$11") (pinfunction "EX_ANT_P$11") (pintype "bidirectional"))
      (node (ref "X4") (pin "P") (pinfunction "ANT_P") (pintype "bidirectional"))
    )
    (net (code "55") (name "Net-(U6-GND-PadP$12)") (class "Default")
      (node (ref "U6") (pin "P$12") (pinfunction "GND_P$12") (pintype "bidirectional"))
      (node (ref "U6") (pin "P$19") (pinfunction "GND_P$19") (pintype "bidirectional"))
    )
    (net (code "56") (name "Net-(U7-ANT)") (class "Default")
      (node (ref "JP7") (pin "1") (pinfunction "1_1") (pintype "passive"))
      (node (ref "U7") (pin "1P") (pinfunction "ANT_1P") (pintype "bidirectional"))
      (node (ref "X3") (pin "P") (pinfunction "ANT_P") (pintype "bidirectional"))
    )
    (net (code "57") (name "Net-(X2B-1)") (class "Default")
      (node (ref "D2") (pin "1") (pinfunction "1_1") (pintype "bidirectional"))
      (node (ref "D3") (pin "A") (pinfunction "A_A") (pintype "passive"))
      (node (ref "X2") (pin "1") (pinfunction "1_1") (pintype "passive"))
      (node (ref "X2") (pin "2") (pinfunction "1_2") (pintype "passive"))
    )
    (net (code "58") (name "unconnected-(IC1-PA0-WKUP-Pad10)") (class "Default")
      (node (ref "IC1") (pin "10") (pinfunction "PA0-WKUP_10") (pintype "bidirectional"))
    )
    (net (code "59") (name "unconnected-(IC1-PA1-Pad11)") (class "Default")
      (node (ref "IC1") (pin "11") (pinfunction "PA1_11") (pintype "bidirectional"))
    )
    (net (code "60") (name "unconnected-(IC1-PA4-Pad14)") (class "Default")
      (node (ref "IC1") (pin "14") (pinfunction "PA4_14") (pintype "bidirectional"))
    )
    (net (code "61") (name "unconnected-(IC1-PA5-Pad15)") (class "Default")
      (node (ref "IC1") (pin "15") (pinfunction "PA5_15") (pintype "bidirectional"))
    )
    (net (code "62") (name "unconnected-(IC1-PA9-Pad30)") (class "Default")
      (node (ref "IC1") (pin "30") (pinfunction "PA9_30") (pintype "bidirectional"))
    )
    (net (code "63") (name "unconnected-(IC1-PA15-Pad38)") (class "Default")
      (node (ref "IC1") (pin "38") (pinfunction "PA15_38") (pintype "bidirectional"))
    )
    (net (code "64") (name "unconnected-(IC1-PB3-Pad39)") (class "Default")
      (node (ref "IC1") (pin "39") (pinfunction "PB3_39") (pintype "bidirectional"))
    )
    (net (code "65") (name "unconnected-(IC1-PB4-Pad40)") (class "Default")
      (node (ref "IC1") (pin "40") (pinfunction "PB4_40") (pintype "bidirectional"))
    )
    (net (code "66") (name "unconnected-(IC1-PB5-Pad41)") (class "Default")
      (node (ref "IC1") (pin "41") (pinfunction "PB5_41") (pintype "bidirectional"))
    )
    (net (code "67") (name "unconnected-(IC1-PB6-Pad42)") (class "Default")
      (node (ref "IC1") (pin "42") (pinfunction "PB6_42") (pintype "bidirectional"))
    )
    (net (code "68") (name "unconnected-(IC1-PB7-Pad43)") (class "Default")
      (node (ref "IC1") (pin "43") (pinfunction "PB7_43") (pintype "bidirectional"))
    )
    (net (code "69") (name "unconnected-(IC1-PB10-Pad21)") (class "Default")
      (node (ref "IC1") (pin "21") (pinfunction "PB10_21") (pintype "bidirectional"))
    )
    (net (code "70") (name "unconnected-(IC1-PC13-TAMPER-RTC-Pad2)") (class "Default")
      (node (ref "IC1") (pin "2") (pinfunction "PC13-TAMPER-RTC_2") (pintype "bidirectional"))
    )
    (net (code "71") (name "unconnected-(IC1-VBAT-Pad1)") (class "Default")
      (node (ref "IC1") (pin "1") (pinfunction "VBAT_1") (pintype "bidirectional"))
    )
    (net (code "72") (name "unconnected-(U1-AUX_CL-Pad7)") (class "Default")
      (node (ref "U1") (pin "7") (pinfunction "AUX_CL_7") (pintype "bidirectional"))
    )
    (net (code "73") (name "unconnected-(U1-AUX_DA-Pad6)") (class "Default")
      (node (ref "U1") (pin "6") (pinfunction "AUX_DA_6") (pintype "bidirectional"))
    )
    (net (code "74") (name "unconnected-(U1-INT-Pad12)") (class "Default")
      (node (ref "U1") (pin "12") (pinfunction "INT_12") (pintype "bidirectional"))
    )
    (net (code "75") (name "unconnected-(U4-INT1-Pad6)") (class "Default")
      (node (ref "U4") (pin "6") (pinfunction "INT1_6") (pintype "bidirectional"))
    )
    (net (code "76") (name "unconnected-(U4-INT2-Pad5)") (class "Default")
      (node (ref "U4") (pin "5") (pinfunction "INT2_5") (pintype "bidirectional"))
    )
    (net (code "77") (name "unconnected-(U6-1PPS-PadP$13)") (class "Default")
      (node (ref "U6") (pin "P$13") (pinfunction "1PPS_P$13") (pintype "bidirectional"))
    )
    (net (code "78") (name "unconnected-(U6-NC-PadP$6)") (class "Default")
      (node (ref "U6") (pin "P$6") (pinfunction "NC_P$6") (pintype "bidirectional"))
    )
    (net (code "79") (name "unconnected-(U6-NC-PadP$7)") (class "Default")
      (node (ref "U6") (pin "P$7") (pinfunction "NC_P$7") (pintype "bidirectional"))
    )
    (net (code "80") (name "unconnected-(U6-NC-PadP$15)") (class "Default")
      (node (ref "U6") (pin "P$15") (pinfunction "NC_P$15") (pintype "bidirectional"))
    )
    (net (code "81") (name "unconnected-(U6-NC-PadP$16)") (class "Default")
      (node (ref "U6") (pin "P$16") (pinfunction "NC_P$16") (pintype "bidirectional"))
    )
    (net (code "82") (name "unconnected-(U6-NC-PadP$17)") (class "Default")
      (node (ref "U6") (pin "P$17") (pinfunction "NC_P$17") (pintype "bidirectional"))
    )
    (net (code "83") (name "unconnected-(U6-NC-PadP$18)") (class "Default")
      (node (ref "U6") (pin "P$18") (pinfunction "NC_P$18") (pintype "bidirectional"))
    )
    (net (code "84") (name "unconnected-(U6-NC-PadP$20)") (class "Default")
      (node (ref "U6") (pin "P$20") (pinfunction "NC_P$20") (pintype "bidirectional"))
    )
    (net (code "85") (name "unconnected-(U6-NRESET-PadP$2)") (class "Default")
      (node (ref "U6") (pin "P$2") (pinfunction "NRESET_P$2") (pintype "bidirectional"))
    )
    (net (code "86") (name "unconnected-(U6-RTCM-PadP$14)") (class "Default")
      (node (ref "U6") (pin "P$14") (pinfunction "RTCM_P$14") (pintype "bidirectional"))
    )
    (net (code "87") (name "unconnected-(U6-VBACKUP-PadP$4)") (class "Default")
      (node (ref "U6") (pin "P$4") (pinfunction "VBACKUP_P$4") (pintype "bidirectional"))
    )
    (net (code "88") (name "unconnected-(U7-DIO1-Pad7P)") (class "Default")
      (node (ref "U7") (pin "7P") (pinfunction "DIO1_7P") (pintype "bidirectional"))
    )
    (net (code "89") (name "unconnected-(U7-DIO2-Pad8P)") (class "Default")
      (node (ref "U7") (pin "8P") (pinfunction "DIO2_8P") (pintype "bidirectional"))
    )
    (net (code "90") (name "unconnected-(U7-DIO3-Pad3P)") (class "Default")
      (node (ref "U7") (pin "3P") (pinfunction "DIO3_3P") (pintype "bidirectional"))
    )
    (net (code "91") (name "unconnected-(U7-DIO4-Pad4P)") (class "Default")
      (node (ref "U7") (pin "4P") (pinfunction "DIO4_4P") (pintype "bidirectional"))
    )
    (net (code "92") (name "unconnected-(U7-DIO5-Pad15P)") (class "Default")
      (node (ref "U7") (pin "15P") (pinfunction "DIO5_15P") (pintype "bidirectional"))
    )
  )
)
